# MainBoard.net
KiCad netlist of a schematic drawn in Altium Designer
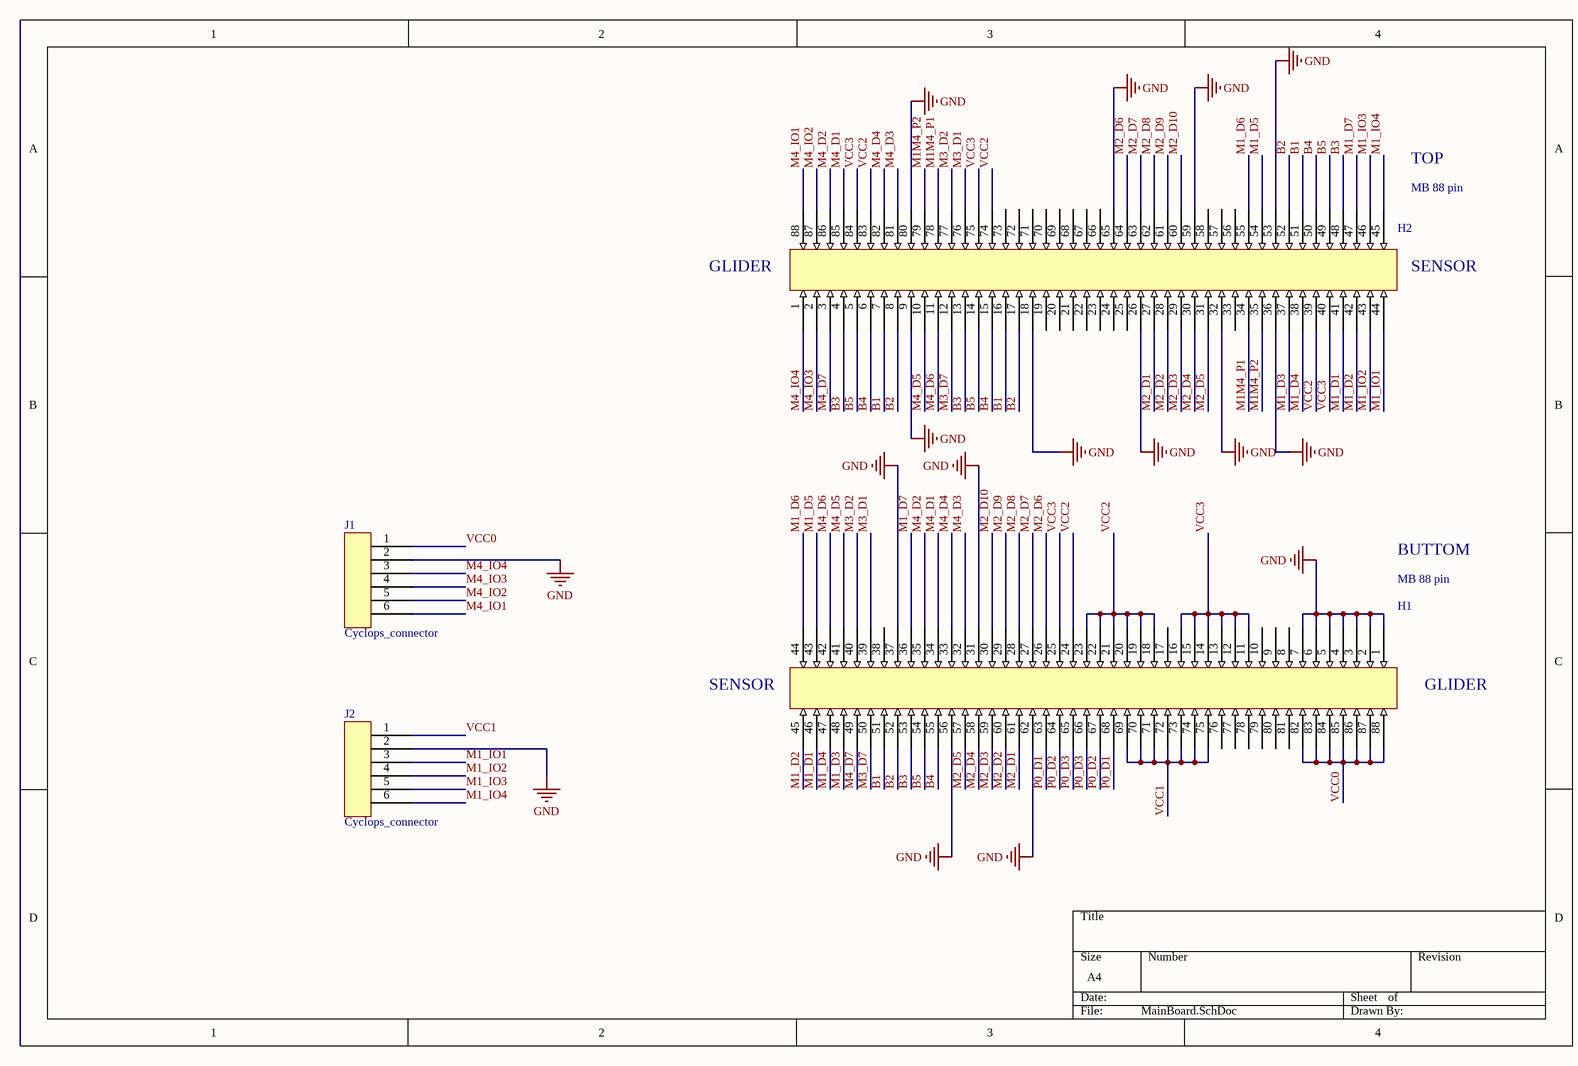
[diagram p0: MainBoard.SchDoc]

(export (version "E")
  (design (tool "Eeschema 10.0.6"))
  (components
    (comp (ref "H1") (value "MB 88 pin") (footprint "MB 88 pins") (libsource (lib "USIB") (part "MB 88 pin")))
    (comp (ref "H2") (value "MB 88 pin") (footprint "MB 88 pins") (libsource (lib "") (part "MB 88 pin_1")))
    (comp (ref "J1")
      (value "Cyclops_connector")
      (footprint "CYCLOPS-1LINE")
      (libsource (lib "Cyclops connector") (part "Cyclops_connector"))
    )
    (comp (ref "J2")
      (value "Cyclops_connector")
      (footprint "CYCLOPS-1LINE")
      (libsource (lib "Cyclops connector") (part "Cyclops_connector"))
    )
  )
  (nets
    (net (code "1") (name "/B1") (class "Default")
      (node (ref "H1") (pin "51") (pintype "input"))
      (node (ref "H2") (pin "16") (pintype "input"))
      (node (ref "H2") (pin "51") (pintype "input"))
      (node (ref "H2") (pin "7") (pintype "input"))
    )
    (net (code "2") (name "/B2") (class "Default")
      (node (ref "H1") (pin "52") (pintype "input"))
      (node (ref "H2") (pin "17") (pintype "input"))
      (node (ref "H2") (pin "52") (pintype "input"))
      (node (ref "H2") (pin "8") (pintype "input"))
    )
    (net (code "3") (name "/B3") (class "Default")
      (node (ref "H1") (pin "53") (pintype "input"))
      (node (ref "H2") (pin "13") (pintype "input"))
      (node (ref "H2") (pin "4") (pintype "input"))
      (node (ref "H2") (pin "48") (pintype "input"))
    )
    (net (code "4") (name "/B4") (class "Default")
      (node (ref "H1") (pin "55") (pintype "input"))
      (node (ref "H2") (pin "15") (pintype "input"))
      (node (ref "H2") (pin "50") (pintype "input"))
      (node (ref "H2") (pin "6") (pintype "input"))
    )
    (net (code "5") (name "/B5") (class "Default")
      (node (ref "H1") (pin "54") (pintype "input"))
      (node (ref "H2") (pin "14") (pintype "input"))
      (node (ref "H2") (pin "49") (pintype "input"))
      (node (ref "H2") (pin "5") (pintype "input"))
    )
    (net (code "6") (name "/M1M4_P1") (class "Default")
      (node (ref "H2") (pin "34") (pintype "input"))
      (node (ref "H2") (pin "78") (pintype "input"))
    )
    (net (code "7") (name "/M1M4_P2") (class "Default")
      (node (ref "H2") (pin "35") (pintype "input"))
      (node (ref "H2") (pin "79") (pintype "input"))
    )
    (net (code "8") (name "/M1_D1") (class "Default")
      (node (ref "H1") (pin "46") (pintype "input"))
      (node (ref "H2") (pin "41") (pintype "input"))
    )
    (net (code "9") (name "/M1_D2") (class "Default")
      (node (ref "H1") (pin "45") (pintype "input"))
      (node (ref "H2") (pin "42") (pintype "input"))
    )
    (net (code "10") (name "/M1_D3") (class "Default")
      (node (ref "H1") (pin "48") (pintype "input"))
      (node (ref "H2") (pin "37") (pintype "input"))
    )
    (net (code "11") (name "/M1_D4") (class "Default")
      (node (ref "H1") (pin "47") (pintype "input"))
      (node (ref "H2") (pin "38") (pintype "input"))
    )
    (net (code "12") (name "/M1_D5") (class "Default")
      (node (ref "H1") (pin "43") (pintype "input"))
      (node (ref "H2") (pin "54") (pintype "input"))
    )
    (net (code "13") (name "/M1_D6") (class "Default")
      (node (ref "H1") (pin "44") (pintype "input"))
      (node (ref "H2") (pin "55") (pintype "input"))
    )
    (net (code "14") (name "/M1_D7") (class "Default")
      (node (ref "H1") (pin "36") (pintype "input"))
      (node (ref "H2") (pin "47") (pintype "input"))
    )
    (net (code "15") (name "/M1_IO1") (class "Default")
      (node (ref "H2") (pin "44") (pintype "input"))
      (node (ref "J2") (pin "3") (pintype "passive"))
    )
    (net (code "16") (name "/M1_IO2") (class "Default")
      (node (ref "H2") (pin "43") (pintype "input"))
      (node (ref "J2") (pin "4") (pintype "passive"))
    )
    (net (code "17") (name "/M1_IO3") (class "Default")
      (node (ref "H2") (pin "46") (pintype "input"))
      (node (ref "J2") (pin "5") (pintype "passive"))
    )
    (net (code "18") (name "/M1_IO4") (class "Default")
      (node (ref "H2") (pin "45") (pintype "input"))
      (node (ref "J2") (pin "6") (pintype "passive"))
    )
    (net (code "19") (name "/M2_D1") (class "Default")
      (node (ref "H1") (pin "61") (pintype "input"))
      (node (ref "H2") (pin "27") (pintype "input"))
    )
    (net (code "20") (name "/M2_D2") (class "Default")
      (node (ref "H1") (pin "60") (pintype "input"))
      (node (ref "H2") (pin "28") (pintype "input"))
    )
    (net (code "21") (name "/M2_D3") (class "Default")
      (node (ref "H1") (pin "59") (pintype "input"))
      (node (ref "H2") (pin "29") (pintype "input"))
    )
    (net (code "22") (name "/M2_D4") (class "Default")
      (node (ref "H1") (pin "58") (pintype "input"))
      (node (ref "H2") (pin "30") (pintype "input"))
    )
    (net (code "23") (name "/M2_D5") (class "Default")
      (node (ref "H1") (pin "57") (pintype "input"))
      (node (ref "H2") (pin "31") (pintype "input"))
    )
    (net (code "24") (name "/M2_D6") (class "Default")
      (node (ref "H1") (pin "26") (pintype "input"))
      (node (ref "H2") (pin "64") (pintype "input"))
    )
    (net (code "25") (name "/M2_D7") (class "Default")
      (node (ref "H1") (pin "27") (pintype "input"))
      (node (ref "H2") (pin "63") (pintype "input"))
    )
    (net (code "26") (name "/M2_D8") (class "Default")
      (node (ref "H1") (pin "28") (pintype "input"))
      (node (ref "H2") (pin "62") (pintype "input"))
    )
    (net (code "27") (name "/M2_D9") (class "Default")
      (node (ref "H1") (pin "29") (pintype "input"))
      (node (ref "H2") (pin "61") (pintype "input"))
    )
    (net (code "28") (name "/M2_D10") (class "Default")
      (node (ref "H1") (pin "30") (pintype "input"))
      (node (ref "H2") (pin "60") (pintype "input"))
    )
    (net (code "29") (name "/M3_D1") (class "Default")
      (node (ref "H1") (pin "39") (pintype "input"))
      (node (ref "H2") (pin "76") (pintype "input"))
    )
    (net (code "30") (name "/M3_D2") (class "Default")
      (node (ref "H1") (pin "40") (pintype "input"))
      (node (ref "H2") (pin "77") (pintype "input"))
    )
    (net (code "31") (name "/M3_D7") (class "Default")
      (node (ref "H1") (pin "50") (pintype "input"))
      (node (ref "H2") (pin "12") (pintype "input"))
    )
    (net (code "32") (name "/M4_D1") (class "Default")
      (node (ref "H1") (pin "34") (pintype "input"))
      (node (ref "H2") (pin "85") (pintype "input"))
    )
    (net (code "33") (name "/M4_D2") (class "Default")
      (node (ref "H1") (pin "35") (pintype "input"))
      (node (ref "H2") (pin "86") (pintype "input"))
    )
    (net (code "34") (name "/M4_D3") (class "Default")
      (node (ref "H1") (pin "32") (pintype "input"))
      (node (ref "H2") (pin "81") (pintype "input"))
    )
    (net (code "35") (name "/M4_D4") (class "Default")
      (node (ref "H1") (pin "33") (pintype "input"))
      (node (ref "H2") (pin "82") (pintype "input"))
    )
    (net (code "36") (name "/M4_D5") (class "Default")
      (node (ref "H1") (pin "41") (pintype "input"))
      (node (ref "H2") (pin "10") (pintype "input"))
    )
    (net (code "37") (name "/M4_D6") (class "Default")
      (node (ref "H1") (pin "42") (pintype "input"))
      (node (ref "H2") (pin "11") (pintype "input"))
    )
    (net (code "38") (name "/M4_D7") (class "Default")
      (node (ref "H1") (pin "49") (pintype "input"))
      (node (ref "H2") (pin "3") (pintype "input"))
    )
    (net (code "39") (name "/M4_IO1") (class "Default")
      (node (ref "H2") (pin "88") (pintype "input"))
      (node (ref "J1") (pin "6") (pintype "passive"))
    )
    (net (code "40") (name "/M4_IO2") (class "Default")
      (node (ref "H2") (pin "87") (pintype "input"))
      (node (ref "J1") (pin "5") (pintype "passive"))
    )
    (net (code "41") (name "/M4_IO3") (class "Default")
      (node (ref "H2") (pin "2") (pintype "input"))
      (node (ref "J1") (pin "4") (pintype "passive"))
    )
    (net (code "42") (name "/M4_IO4") (class "Default")
      (node (ref "H2") (pin "1") (pintype "input"))
      (node (ref "J1") (pin "3") (pintype "passive"))
    )
    (net (code "43") (name "/P0_D1") (class "Default")
      (node (ref "H1") (pin "63") (pintype "input"))
      (node (ref "H1") (pin "68") (pintype "input"))
    )
    (net (code "44") (name "/P0_D2") (class "Default")
      (node (ref "H1") (pin "64") (pintype "input"))
      (node (ref "H1") (pin "67") (pintype "input"))
    )
    (net (code "45") (name "/P0_D3") (class "Default")
      (node (ref "H1") (pin "65") (pintype "input"))
      (node (ref "H1") (pin "66") (pintype "input"))
    )
    (net (code "46") (name "/VCC0") (class "Default")
      (node (ref "H1") (pin "82") (pintype "input"))
      (node (ref "H1") (pin "83") (pintype "input"))
      (node (ref "H1") (pin "84") (pintype "input"))
      (node (ref "H1") (pin "85") (pintype "input"))
      (node (ref "H1") (pin "86") (pintype "input"))
      (node (ref "H1") (pin "87") (pintype "input"))
      (node (ref "H1") (pin "88") (pintype "input"))
      (node (ref "J1") (pin "1") (pintype "passive"))
    )
    (net (code "47") (name "/VCC1") (class "Default")
      (node (ref "H1") (pin "69") (pintype "input"))
      (node (ref "H1") (pin "70") (pintype "input"))
      (node (ref "H1") (pin "71") (pintype "input"))
      (node (ref "H1") (pin "72") (pintype "input"))
      (node (ref "H1") (pin "73") (pintype "input"))
      (node (ref "H1") (pin "74") (pintype "input"))
      (node (ref "H1") (pin "75") (pintype "input"))
      (node (ref "J2") (pin "1") (pintype "passive"))
    )
    (net (code "48") (name "/VCC2") (class "Default")
      (node (ref "H1") (pin "18") (pintype "input"))
      (node (ref "H1") (pin "19") (pintype "input"))
      (node (ref "H1") (pin "20") (pintype "input"))
      (node (ref "H1") (pin "21") (pintype "input"))
      (node (ref "H1") (pin "22") (pintype "input"))
      (node (ref "H1") (pin "23") (pintype "input"))
      (node (ref "H1") (pin "24") (pintype "input"))
      (node (ref "H2") (pin "39") (pintype "input"))
      (node (ref "H2") (pin "74") (pintype "input"))
      (node (ref "H2") (pin "83") (pintype "input"))
    )
    (net (code "49") (name "/VCC3") (class "Default")
      (node (ref "H1") (pin "11") (pintype "input"))
      (node (ref "H1") (pin "12") (pintype "input"))
      (node (ref "H1") (pin "13") (pintype "input"))
      (node (ref "H1") (pin "14") (pintype "input"))
      (node (ref "H1") (pin "15") (pintype "input"))
      (node (ref "H1") (pin "16") (pintype "input"))
      (node (ref "H1") (pin "25") (pintype "input"))
      (node (ref "H2") (pin "40") (pintype "input"))
      (node (ref "H2") (pin "75") (pintype "input"))
      (node (ref "H2") (pin "84") (pintype "input"))
    )
    (net (code "50") (name "GND") (class "Default")
      (node (ref "H1") (pin "1") (pintype "input"))
      (node (ref "H1") (pin "2") (pintype "input"))
      (node (ref "H1") (pin "3") (pintype "input"))
      (node (ref "H1") (pin "31") (pintype "input"))
      (node (ref "H1") (pin "37") (pintype "input"))
      (node (ref "H1") (pin "4") (pintype "input"))
      (node (ref "H1") (pin "5") (pintype "input"))
      (node (ref "H1") (pin "56") (pintype "input"))
      (node (ref "H1") (pin "6") (pintype "input"))
      (node (ref "H1") (pin "62") (pintype "input"))
      (node (ref "H1") (pin "7") (pintype "input"))
      (node (ref "H2") (pin "18") (pintype "input"))
      (node (ref "H2") (pin "26") (pintype "input"))
      (node (ref "H2") (pin "32") (pintype "input"))
      (node (ref "H2") (pin "36") (pintype "input"))
      (node (ref "H2") (pin "53") (pintype "input"))
      (node (ref "H2") (pin "59") (pintype "input"))
      (node (ref "H2") (pin "65") (pintype "input"))
      (node (ref "H2") (pin "80") (pintype "input"))
      (node (ref "H2") (pin "9") (pintype "input"))
      (node (ref "J1") (pin "2") (pintype "passive"))
      (node (ref "J2") (pin "2") (pintype "passive"))
    )
    (net (code "51") (name "unconnected-(H1-Pad8)") (class "Default")
      (node (ref "H1") (pin "8") (pintype "input"))
    )
    (net (code "52") (name "unconnected-(H1-Pad9)") (class "Default")
      (node (ref "H1") (pin "9") (pintype "input"))
    )
    (net (code "53") (name "unconnected-(H1-Pad10)") (class "Default")
      (node (ref "H1") (pin "10") (pintype "input"))
    )
    (net (code "54") (name "unconnected-(H1-Pad17)") (class "Default")
      (node (ref "H1") (pin "17") (pintype "input"))
    )
    (net (code "55") (name "unconnected-(H1-Pad38)") (class "Default")
      (node (ref "H1") (pin "38") (pintype "input"))
    )
    (net (code "56") (name "unconnected-(H1-Pad76)") (class "Default")
      (node (ref "H1") (pin "76") (pintype "input"))
    )
    (net (code "57") (name "unconnected-(H1-Pad77)") (class "Default")
      (node (ref "H1") (pin "77") (pintype "input"))
    )
    (net (code "58") (name "unconnected-(H1-Pad78)") (class "Default")
      (node (ref "H1") (pin "78") (pintype "input"))
    )
    (net (code "59") (name "unconnected-(H1-Pad79)") (class "Default")
      (node (ref "H1") (pin "79") (pintype "input"))
    )
    (net (code "60") (name "unconnected-(H1-Pad80)") (class "Default")
      (node (ref "H1") (pin "80") (pintype "input"))
    )
    (net (code "61") (name "unconnected-(H1-Pad81)") (class "Default")
      (node (ref "H1") (pin "81") (pintype "input"))
    )
    (net (code "62") (name "unconnected-(H2-Pad19)") (class "Default")
      (node (ref "H2") (pin "19") (pintype "input"))
    )
    (net (code "63") (name "unconnected-(H2-Pad20)") (class "Default")
      (node (ref "H2") (pin "20") (pintype "input"))
    )
    (net (code "64") (name "unconnected-(H2-Pad21)") (class "Default")
      (node (ref "H2") (pin "21") (pintype "input"))
    )
    (net (code "65") (name "unconnected-(H2-Pad22)") (class "Default")
      (node (ref "H2") (pin "22") (pintype "input"))
    )
    (net (code "66") (name "unconnected-(H2-Pad23)") (class "Default")
      (node (ref "H2") (pin "23") (pintype "input"))
    )
    (net (code "67") (name "unconnected-(H2-Pad24)") (class "Default")
      (node (ref "H2") (pin "24") (pintype "input"))
    )
    (net (code "68") (name "unconnected-(H2-Pad25)") (class "Default")
      (node (ref "H2") (pin "25") (pintype "input"))
    )
    (net (code "69") (name "unconnected-(H2-Pad33)") (class "Default")
      (node (ref "H2") (pin "33") (pintype "input"))
    )
    (net (code "70") (name "unconnected-(H2-Pad56)") (class "Default")
      (node (ref "H2") (pin "56") (pintype "input"))
    )
    (net (code "71") (name "unconnected-(H2-Pad57)") (class "Default")
      (node (ref "H2") (pin "57") (pintype "input"))
    )
    (net (code "72") (name "unconnected-(H2-Pad58)") (class "Default")
      (node (ref "H2") (pin "58") (pintype "input"))
    )
    (net (code "73") (name "unconnected-(H2-Pad66)") (class "Default")
      (node (ref "H2") (pin "66") (pintype "input"))
    )
    (net (code "74") (name "unconnected-(H2-Pad67)") (class "Default")
      (node (ref "H2") (pin "67") (pintype "input"))
    )
    (net (code "75") (name "unconnected-(H2-Pad68)") (class "Default")
      (node (ref "H2") (pin "68") (pintype "input"))
    )
    (net (code "76") (name "unconnected-(H2-Pad69)") (class "Default")
      (node (ref "H2") (pin "69") (pintype "input"))
    )
    (net (code "77") (name "unconnected-(H2-Pad70)") (class "Default")
      (node (ref "H2") (pin "70") (pintype "input"))
    )
    (net (code "78") (name "unconnected-(H2-Pad71)") (class "Default")
      (node (ref "H2") (pin "71") (pintype "input"))
    )
    (net (code "79") (name "unconnected-(H2-Pad72)") (class "Default")
      (node (ref "H2") (pin "72") (pintype "input"))
    )
    (net (code "80") (name "unconnected-(H2-Pad73)") (class "Default")
      (node (ref "H2") (pin "73") (pintype "input"))
    )
  )
)
